# probe20mm.net
KiCad netlist of a schematic drawn in EAGLE
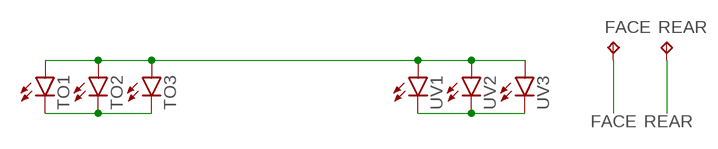
[diagram p0: schematic, sheet 1]

(export (version "E")
  (design (tool "Eeschema 10.0.6"))
  (components
    (comp (ref "FACE")
      (value "TPTP10R")
      (footprint "eagle-import:TP10R")
      (libsource (lib "eagle-import") (part "TPTP10R"))
    )
    (comp (ref "REAR")
      (value "TPTP10R")
      (footprint "eagle-import:TP10R")
      (libsource (lib "eagle-import") (part "TPTP10R"))
    )
    (comp (ref "TO1")
      (value "LED5MM")
      (footprint "eagle-import:LED5MM")
      (libsource (lib "eagle-import") (part "LED5MM"))
    )
    (comp (ref "TO2")
      (value "LED5MM")
      (footprint "eagle-import:LED5MM")
      (libsource (lib "eagle-import") (part "LED5MM"))
    )
    (comp (ref "TO3")
      (value "LED5MM")
      (footprint "eagle-import:LED5MM")
      (libsource (lib "eagle-import") (part "LED5MM"))
    )
    (comp (ref "UV1")
      (value "LED5MM")
      (footprint "eagle-import:LED5MM")
      (libsource (lib "eagle-import") (part "LED5MM"))
    )
    (comp (ref "UV2")
      (value "LED5MM")
      (footprint "eagle-import:LED5MM")
      (libsource (lib "eagle-import") (part "LED5MM"))
    )
    (comp (ref "UV3")
      (value "LED5MM")
      (footprint "eagle-import:LED5MM")
      (libsource (lib "eagle-import") (part "LED5MM"))
    )
  )
  (nets
    (net (code "1") (name "/FACE") (class "Default")
      (node (ref "FACE") (pin "TP") (pinfunction "TP_TP") (pintype "input"))
    )
    (net (code "2") (name "/REAR") (class "Default")
      (node (ref "REAR") (pin "TP") (pinfunction "TP_TP") (pintype "input"))
    )
    (net (code "3") (name "Net-(TO1-C)") (class "Default")
      (node (ref "TO1") (pin "K") (pinfunction "C_K") (pintype "passive"))
      (node (ref "TO2") (pin "K") (pinfunction "C_K") (pintype "passive"))
      (node (ref "TO3") (pin "K") (pinfunction "C_K") (pintype "passive"))
    )
    (net (code "4") (name "Net-(TO1-PadA)") (class "Default")
      (node (ref "TO1") (pin "A") (pinfunction "A_A") (pintype "passive"))
      (node (ref "TO2") (pin "A") (pinfunction "A_A") (pintype "passive"))
      (node (ref "TO3") (pin "A") (pinfunction "A_A") (pintype "passive"))
      (node (ref "UV1") (pin "A") (pinfunction "A_A") (pintype "passive"))
      (node (ref "UV2") (pin "A") (pinfunction "A_A") (pintype "passive"))
      (node (ref "UV3") (pin "A") (pinfunction "A_A") (pintype "passive"))
    )
    (net (code "5") (name "Net-(UV1-C)") (class "Default")
      (node (ref "UV1") (pin "K") (pinfunction "C_K") (pintype "passive"))
      (node (ref "UV2") (pin "K") (pinfunction "C_K") (pintype "passive"))
      (node (ref "UV3") (pin "K") (pinfunction "C_K") (pintype "passive"))
    )
  )
)
